# usbuc.net
KiCad netlist of a schematic drawn in EAGLE
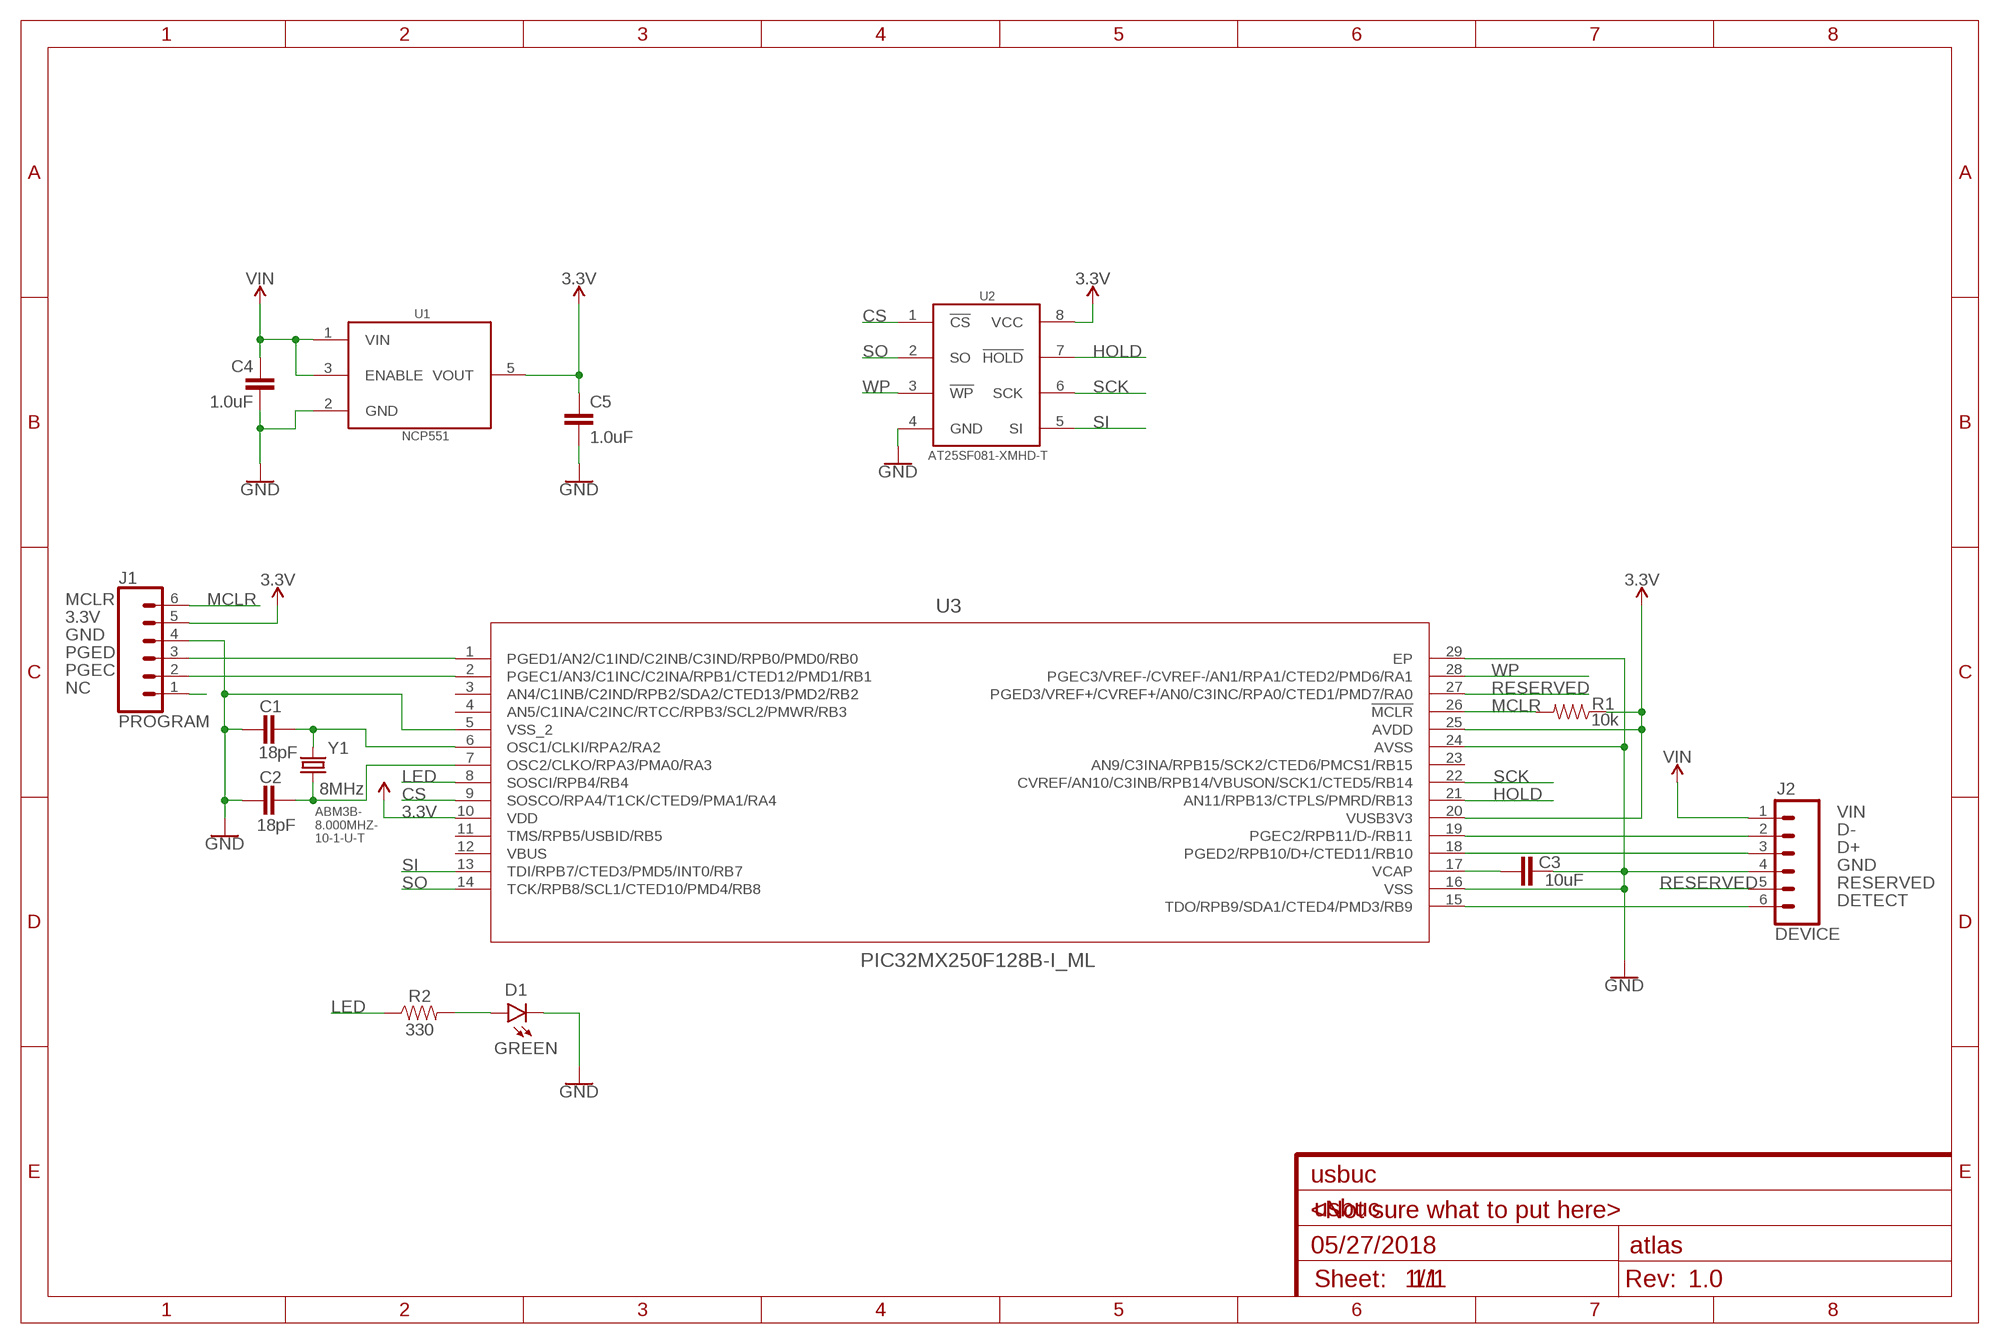
[diagram p0: schematic, sheet 1]

(export (version "E")
  (design (tool "Eeschema 10.0.6"))
  (components
    (comp (ref "C1")
      (value "18pF")
      (footprint "eagle-import:0603")
      (libsource (lib "eagle-import") (part "18PF-0603-50V-5%"))
    )
    (comp (ref "C2")
      (value "18pF")
      (footprint "eagle-import:0603")
      (libsource (lib "eagle-import") (part "18PF-0603-50V-5%"))
    )
    (comp (ref "C3")
      (value "10uF")
      (footprint "eagle-import:0603")
      (libsource (lib "eagle-import") (part "10UF-0603-6.3V-20%"))
    )
    (comp (ref "C4")
      (value "1.0uF")
      (footprint "eagle-import:0603")
      (libsource (lib "eagle-import") (part "1.0UF-0603-16V-10%"))
    )
    (comp (ref "C5")
      (value "1.0uF")
      (footprint "eagle-import:0603")
      (libsource (lib "eagle-import") (part "1.0UF-0603-16V-10%"))
    )
    (comp (ref "D1")
      (value "GREEN")
      (footprint "eagle-import:LED-0603")
      (libsource (lib "eagle-import") (part "LED-GREEN0603"))
    )
    (comp (ref "J1")
      (value "PROGRAM")
      (footprint "eagle-import:1X06_FEMALE_LOCK.010")
      (libsource (lib "eagle-import") (part "CONN_06FEMALE_LOCK"))
    )
    (comp (ref "J2")
      (value "DEVICE")
      (footprint "eagle-import:1X06_LONGPADS")
      (libsource (lib "eagle-import") (part "CONN_06LONGPADS"))
    )
    (comp (ref "R1")
      (value "10k")
      (footprint "eagle-import:0603")
      (libsource (lib "eagle-import") (part "10KOHM-0603-1/10W-1%"))
    )
    (comp (ref "R2")
      (value "330")
      (footprint "eagle-import:0603")
      (libsource (lib "eagle-import") (part "330OHM-0603-1/10W-1%"))
    )
    (comp (ref "U1")
      (value "NCP551")
      (footprint "eagle-import:TSOP-5")
      (libsource (lib "eagle-import") (part "NCP551"))
    )
    (comp (ref "U2")
      (value "AT25SF081-XMHD-T")
      (footprint "eagle-import:TSSOP8")
      (libsource (lib "eagle-import") (part "AT25SF081-XMHD-T"))
    )
    (comp (ref "U3")
      (value "PIC32MX250F128B-I_ML")
      (footprint "eagle-import:QFN28_6X6MC")
      (libsource (lib "eagle-import") (part "PIC32MX250F128B-I_ML"))
    )
    (comp (ref "Y1")
      (value "8MHz")
      (footprint "eagle-import:CRYSTAL-SMD-5X3.2-4PAD")
      (libsource (lib "eagle-import") (part "CRYSTAL-8MHZSMD-5X3.2"))
    )
  )
  (nets
    (net (code "1") (name "/CS") (class "Default")
      (node (ref "U2") (pin "1") (pinfunction "~{CS}_1") (pintype "input"))
      (node (ref "U3") (pin "9") (pinfunction "SOSCO/RPA4/T1CK/CTED9/PMA1/RA4_9") (pintype "bidirectional"))
    )
    (net (code "2") (name "/D+") (class "Default")
      (node (ref "J2") (pin "3") (pinfunction "3_3") (pintype "passive"))
      (node (ref "U3") (pin "18") (pinfunction "PGED2/RPB10/D+/CTED11/RB10_18") (pintype "bidirectional"))
    )
    (net (code "3") (name "/D-") (class "Default")
      (node (ref "J2") (pin "2") (pinfunction "2_2") (pintype "passive"))
      (node (ref "U3") (pin "19") (pinfunction "PGEC2/RPB11/D-/RB11_19") (pintype "bidirectional"))
    )
    (net (code "4") (name "/DETECT") (class "Default")
      (node (ref "J2") (pin "6") (pinfunction "6_6") (pintype "passive"))
      (node (ref "U3") (pin "15") (pinfunction "TDO/RPB9/SDA1/CTED4/PMD3/RB9_15") (pintype "bidirectional"))
    )
    (net (code "5") (name "/HOLD") (class "Default")
      (node (ref "U2") (pin "7") (pinfunction "~{HOLD}_7") (pintype "bidirectional"))
      (node (ref "U3") (pin "21") (pinfunction "AN11/RPB13/CTPLS/PMRD/RB13_21") (pintype "bidirectional"))
    )
    (net (code "6") (name "/LED") (class "Default")
      (node (ref "R2") (pin "1") (pinfunction "1_1") (pintype "passive"))
      (node (ref "U3") (pin "8") (pinfunction "SOSCI/RPB4/RB4_8") (pintype "bidirectional"))
    )
    (net (code "7") (name "/MCLR") (class "Default")
      (node (ref "J1") (pin "6") (pinfunction "6_6") (pintype "passive"))
      (node (ref "R1") (pin "2") (pinfunction "2_2") (pintype "passive"))
      (node (ref "U3") (pin "26") (pinfunction "~{MCLR}_26") (pintype "input"))
    )
    (net (code "8") (name "/NC") (class "Default")
      (node (ref "J1") (pin "1") (pinfunction "1_1") (pintype "passive"))
    )
    (net (code "9") (name "/PGEC") (class "Default")
      (node (ref "J1") (pin "2") (pinfunction "2_2") (pintype "passive"))
      (node (ref "U3") (pin "2") (pinfunction "PGEC1/AN3/C1INC/C2INA/RPB1/CTED12/PMD1/RB1_2") (pintype "bidirectional"))
    )
    (net (code "10") (name "/PGED") (class "Default")
      (node (ref "J1") (pin "3") (pinfunction "3_3") (pintype "passive"))
      (node (ref "U3") (pin "1") (pinfunction "PGED1/AN2/C1IND/C2INB/C3IND/RPB0/PMD0/RB0_1") (pintype "bidirectional"))
    )
    (net (code "11") (name "/RESERVED") (class "Default")
      (node (ref "J2") (pin "5") (pinfunction "5_5") (pintype "passive"))
      (node (ref "U3") (pin "27") (pinfunction "PGED3/VREF+/CVREF+/AN0/C3INC/RPA0/CTED1/PMD7/RA0_27") (pintype "bidirectional"))
    )
    (net (code "12") (name "/SCK") (class "Default")
      (node (ref "U2") (pin "6") (pinfunction "SCK_6") (pintype "input"))
      (node (ref "U3") (pin "22") (pinfunction "CVREF/AN10/C3INB/RPB14/VBUSON/SCK1/CTED5/RB14_22") (pintype "bidirectional"))
    )
    (net (code "13") (name "/SI") (class "Default")
      (node (ref "U2") (pin "5") (pinfunction "SI_5") (pintype "bidirectional"))
      (node (ref "U3") (pin "13") (pinfunction "TDI/RPB7/CTED3/PMD5/INT0/RB7_13") (pintype "bidirectional"))
    )
    (net (code "14") (name "/SO") (class "Default")
      (node (ref "U2") (pin "2") (pinfunction "SO_2") (pintype "bidirectional"))
      (node (ref "U3") (pin "14") (pinfunction "TCK/RPB8/SCL1/CTED10/PMD4/RB8_14") (pintype "bidirectional"))
    )
    (net (code "15") (name "/VBUS") (class "Default")
      (node (ref "U3") (pin "12") (pinfunction "VBUS_12") (pintype "power_in"))
    )
    (net (code "16") (name "/WP") (class "Default")
      (node (ref "U2") (pin "3") (pinfunction "~{WP}_3") (pintype "bidirectional"))
      (node (ref "U3") (pin "28") (pinfunction "PGEC3/VREF-/CVREF-/AN1/RPA1/CTED2/PMD6/RA1_28") (pintype "bidirectional"))
    )
    (net (code "17") (name "3.3V") (class "Default")
      (node (ref "C5") (pin "1") (pinfunction "1_1") (pintype "passive"))
      (node (ref "J1") (pin "5") (pinfunction "5_5") (pintype "passive"))
      (node (ref "R1") (pin "1") (pinfunction "1_1") (pintype "passive"))
      (node (ref "U1") (pin "5") (pinfunction "VOUT_5") (pintype "power_in"))
      (node (ref "U2") (pin "8") (pinfunction "VCC_8") (pintype "power_in"))
      (node (ref "U3") (pin "10") (pinfunction "VDD_10") (pintype "power_in"))
      (node (ref "U3") (pin "20") (pinfunction "VUSB3V3_20") (pintype "power_in"))
      (node (ref "U3") (pin "25") (pinfunction "AVDD_25") (pintype "power_in"))
    )
    (net (code "18") (name "GND") (class "Default")
      (node (ref "C1") (pin "1") (pinfunction "1_1") (pintype "passive"))
      (node (ref "C2") (pin "1") (pinfunction "1_1") (pintype "passive"))
      (node (ref "C3") (pin "2") (pinfunction "2_2") (pintype "passive"))
      (node (ref "C4") (pin "2") (pinfunction "2_2") (pintype "passive"))
      (node (ref "C5") (pin "2") (pinfunction "2_2") (pintype "passive"))
      (node (ref "D1") (pin "C") (pinfunction "C_C") (pintype "passive"))
      (node (ref "J1") (pin "4") (pinfunction "4_4") (pintype "passive"))
      (node (ref "J2") (pin "4") (pinfunction "4_4") (pintype "passive"))
      (node (ref "U1") (pin "2") (pinfunction "GND_2") (pintype "power_in"))
      (node (ref "U2") (pin "4") (pinfunction "GND_4") (pintype "power_in"))
      (node (ref "U3") (pin "16") (pinfunction "VSS_16") (pintype "power_in"))
      (node (ref "U3") (pin "24") (pinfunction "AVSS_24") (pintype "power_in"))
      (node (ref "U3") (pin "29") (pinfunction "EP_29") (pintype "passive"))
      (node (ref "U3") (pin "5") (pinfunction "VSS_2_5") (pintype "power_in"))
    )
    (net (code "19") (name "Net-(D1-PadA)") (class "Default")
      (node (ref "D1") (pin "A") (pinfunction "A_A") (pintype "passive"))
      (node (ref "R2") (pin "2") (pinfunction "2_2") (pintype "passive"))
    )
    (net (code "20") (name "Net-(U3-OSC1{slash}CLKI{slash}RPA2{slash}RA2)") (class "Default")
      (node (ref "C1") (pin "2") (pinfunction "2_2") (pintype "passive"))
      (node (ref "U3") (pin "6") (pinfunction "OSC1/CLKI/RPA2/RA2_6") (pintype "bidirectional"))
      (node (ref "Y1") (pin "3") (pinfunction "2_3") (pintype "passive"))
    )
    (net (code "21") (name "Net-(U3-OSC2{slash}CLKO{slash}RPA3{slash}PMA0{slash}RA3)") (class "Default")
      (node (ref "C2") (pin "2") (pinfunction "2_2") (pintype "passive"))
      (node (ref "U3") (pin "7") (pinfunction "OSC2/CLKO/RPA3/PMA0/RA3_7") (pintype "bidirectional"))
      (node (ref "Y1") (pin "1") (pinfunction "1_1") (pintype "passive"))
    )
    (net (code "22") (name "Net-(U3-VCAP)") (class "Default")
      (node (ref "C3") (pin "1") (pinfunction "1_1") (pintype "passive"))
      (node (ref "U3") (pin "17") (pinfunction "VCAP_17") (pintype "power_in"))
    )
    (net (code "23") (name "VIN") (class "Default")
      (node (ref "C4") (pin "1") (pinfunction "1_1") (pintype "passive"))
      (node (ref "J2") (pin "1") (pinfunction "1_1") (pintype "passive"))
      (node (ref "U1") (pin "1") (pinfunction "VIN_1") (pintype "power_in"))
      (node (ref "U1") (pin "3") (pinfunction "ENABLE_3") (pintype "input"))
    )
    (net (code "24") (name "unconnected-(U3-AN4{slash}C1INB{slash}C2IND{slash}RPB2{slash}SDA2{slash}CTED13{slash}PMD2{slash}RB2-Pad3)") (class "Default")
      (node (ref "U3") (pin "3") (pinfunction "AN4/C1INB/C2IND/RPB2/SDA2/CTED13/PMD2/RB2_3") (pintype "bidirectional"))
    )
    (net (code "25") (name "unconnected-(U3-AN5{slash}C1INA{slash}C2INC{slash}RTCC{slash}RPB3{slash}SCL2{slash}PMWR{slash}RB3-Pad4)") (class "Default")
      (node (ref "U3") (pin "4") (pinfunction "AN5/C1INA/C2INC/RTCC/RPB3/SCL2/PMWR/RB3_4") (pintype "bidirectional"))
    )
    (net (code "26") (name "unconnected-(U3-AN9{slash}C3INA{slash}RPB15{slash}SCK2{slash}CTED6{slash}PMCS1{slash}RB15-Pad23)") (class "Default")
      (node (ref "U3") (pin "23") (pinfunction "AN9/C3INA/RPB15/SCK2/CTED6/PMCS1/RB15_23") (pintype "bidirectional"))
    )
    (net (code "27") (name "unconnected-(U3-TMS{slash}RPB5{slash}USBID{slash}RB5-Pad11)") (class "Default")
      (node (ref "U3") (pin "11") (pinfunction "TMS/RPB5/USBID/RB5_11") (pintype "bidirectional"))
    )
  )
)
